# STM32F303CCT6.net
KiCad netlist of a schematic drawn in Altium Designer
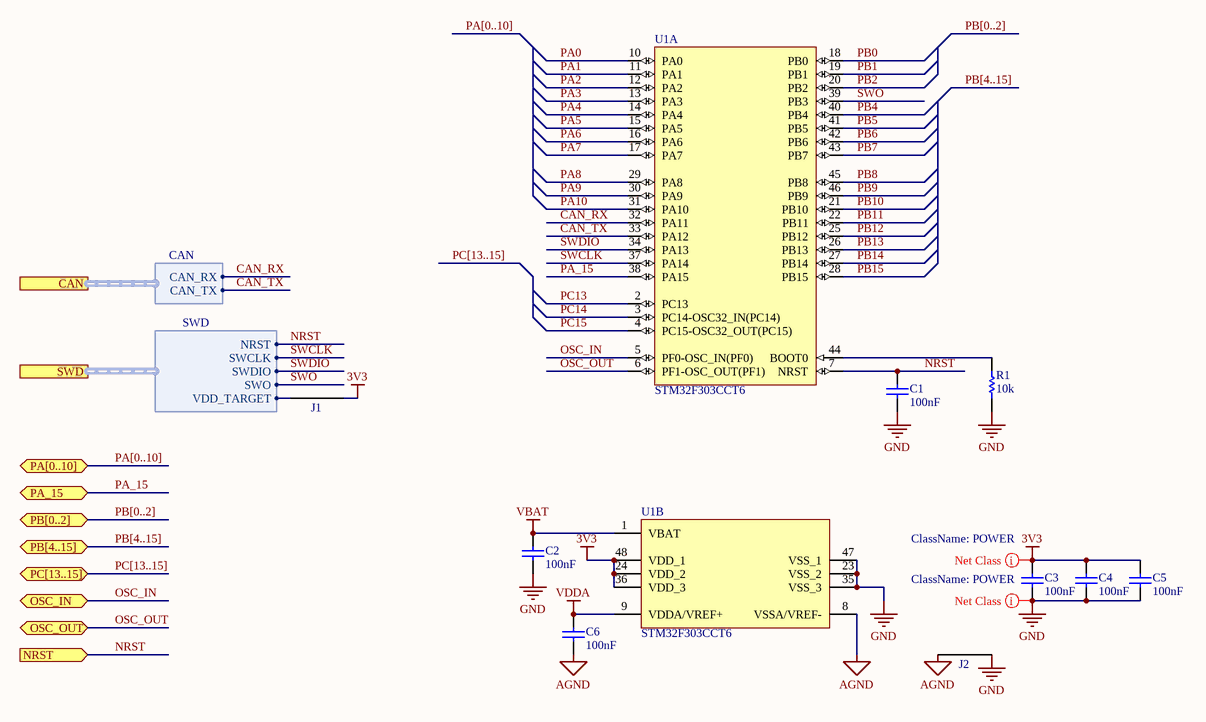
[diagram p0: STM32F303CCT6.SchDoc]

(export (version "E")
  (design (tool "Eeschema 10.0.6"))
  (components
    (comp (ref "C1")
      (value "100nF")
      (footprint "agh_racing_2018:CAP_0603_IPC_MD")
      (description "Capacitor")
      (fields (field (name "Comment") "Cap"))
      (libsource (lib "agh_racing_2018") (part "Cap"))
    )
    (comp (ref "C2")
      (value "100nF")
      (footprint "agh_racing_2018:CAP_0603_IPC_MD")
      (description "Capacitor")
      (fields (field (name "Comment") "Cap"))
      (libsource (lib "agh_racing_2018") (part "Cap"))
    )
    (comp (ref "C3")
      (value "100nF")
      (footprint "agh_racing_2018:CAP_0603_IPC_MD")
      (description "Capacitor")
      (fields (field (name "Comment") "Cap"))
      (libsource (lib "agh_racing_2018") (part "Cap"))
    )
    (comp (ref "C4")
      (value "100nF")
      (footprint "agh_racing_2018:CAP_0603_IPC_MD")
      (description "Capacitor")
      (fields (field (name "Comment") "Cap"))
      (libsource (lib "agh_racing_2018") (part "Cap"))
    )
    (comp (ref "C5")
      (value "100nF")
      (footprint "agh_racing_2018:CAP_0603_IPC_MD")
      (description "Capacitor")
      (fields (field (name "Comment") "Cap"))
      (libsource (lib "agh_racing_2018") (part "Cap"))
    )
    (comp (ref "C6")
      (value "100nF")
      (footprint "agh_racing_2018:CAP_0603_IPC_MD")
      (description "Capacitor")
      (fields (field (name "Comment") "Cap"))
      (libsource (lib "agh_racing_2018") (part "Cap"))
    )
    (comp (ref "J1")
      (value "NetTie")
      (footprint "NETTIE")
      (libsource (lib "Schematic Library") (part "NetTie"))
    )
    (comp (ref "J2")
      (value "NetTie")
      (footprint "agh_racing_2018:NETTIE")
      (libsource (lib "agh_racing_2018") (part "NetTie"))
    )
    (comp (ref "R1")
      (value "10k")
      (footprint "agh_racing_2018:RES_0603_IPC_HD")
      (description "Resistor")
      (fields (field (name "Comment") "Res"))
      (libsource (lib "agh_racing_2018") (part "Res"))
    )
    (comp (ref "U1")
      (value "STM32F303CCT6")
      (footprint "agh_racing_2018:LQFP48_IPC_LD")
      (libsource (lib "agh_racing_2018") (part "STM32F303CCT6"))
    )
  )
  (nets
    (net (code "3") (name "/CAN_RX") (class "Default")
      (node (ref "U1") (pin "32") (pinfunction "PA11_32") (pintype "bidirectional"))
    )
    (net (code "4") (name "/CAN_TX") (class "Default")
      (node (ref "U1") (pin "33") (pinfunction "PA12_33") (pintype "bidirectional"))
    )
    (net (code "5") (name "/NRST") (class "Default")
      (node (ref "C1") (pin "2") (pinfunction "2_2") (pintype "passive"))
      (node (ref "U1") (pin "7") (pinfunction "NRST_7") (pintype "bidirectional"))
    )
    (net (code "6") (name "/OSC_IN") (class "Default")
      (node (ref "U1") (pin "5") (pinfunction "PF0-OSC_IN(PF0)_5") (pintype "bidirectional"))
    )
    (net (code "7") (name "/OSC_OUT") (class "Default")
      (node (ref "U1") (pin "6") (pinfunction "PF1-OSC_OUT(PF1)_6") (pintype "bidirectional"))
    )
    (net (code "8") (name "/PA0") (class "Default")
      (node (ref "U1") (pin "10") (pinfunction "PA0_10") (pintype "bidirectional"))
    )
    (net (code "9") (name "/PA1") (class "Default")
      (node (ref "U1") (pin "11") (pinfunction "PA1_11") (pintype "bidirectional"))
    )
    (net (code "10") (name "/PA2") (class "Default")
      (node (ref "U1") (pin "12") (pinfunction "PA2_12") (pintype "bidirectional"))
    )
    (net (code "11") (name "/PA3") (class "Default")
      (node (ref "U1") (pin "13") (pinfunction "PA3_13") (pintype "bidirectional"))
    )
    (net (code "12") (name "/PA4") (class "Default")
      (node (ref "U1") (pin "14") (pinfunction "PA4_14") (pintype "bidirectional"))
    )
    (net (code "13") (name "/PA5") (class "Default")
      (node (ref "U1") (pin "15") (pinfunction "PA5_15") (pintype "bidirectional"))
    )
    (net (code "14") (name "/PA6") (class "Default")
      (node (ref "U1") (pin "16") (pinfunction "PA6_16") (pintype "bidirectional"))
    )
    (net (code "15") (name "/PA7") (class "Default")
      (node (ref "U1") (pin "17") (pinfunction "PA7_17") (pintype "bidirectional"))
    )
    (net (code "16") (name "/PA8") (class "Default")
      (node (ref "U1") (pin "29") (pinfunction "PA8_29") (pintype "bidirectional"))
    )
    (net (code "17") (name "/PA9") (class "Default")
      (node (ref "U1") (pin "30") (pinfunction "PA9_30") (pintype "bidirectional"))
    )
    (net (code "18") (name "/PA10") (class "Default")
      (node (ref "U1") (pin "31") (pinfunction "PA10_31") (pintype "bidirectional"))
    )
    (net (code "20") (name "/PA_15") (class "Default")
      (node (ref "U1") (pin "38") (pinfunction "PA15_38") (pintype "bidirectional"))
    )
    (net (code "21") (name "/PB0") (class "Default")
      (node (ref "U1") (pin "18") (pinfunction "PB0_18") (pintype "bidirectional"))
    )
    (net (code "22") (name "/PB1") (class "Default")
      (node (ref "U1") (pin "19") (pinfunction "PB1_19") (pintype "bidirectional"))
    )
    (net (code "23") (name "/PB2") (class "Default")
      (node (ref "U1") (pin "20") (pinfunction "PB2_20") (pintype "bidirectional"))
    )
    (net (code "24") (name "/PB4") (class "Default")
      (node (ref "U1") (pin "40") (pinfunction "PB4_40") (pintype "bidirectional"))
    )
    (net (code "25") (name "/PB5") (class "Default")
      (node (ref "U1") (pin "41") (pinfunction "PB5_41") (pintype "bidirectional"))
    )
    (net (code "26") (name "/PB6") (class "Default")
      (node (ref "U1") (pin "42") (pinfunction "PB6_42") (pintype "bidirectional"))
    )
    (net (code "27") (name "/PB7") (class "Default")
      (node (ref "U1") (pin "43") (pinfunction "PB7_43") (pintype "bidirectional"))
    )
    (net (code "28") (name "/PB8") (class "Default")
      (node (ref "U1") (pin "45") (pinfunction "PB8_45") (pintype "bidirectional"))
    )
    (net (code "29") (name "/PB9") (class "Default")
      (node (ref "U1") (pin "46") (pinfunction "PB9_46") (pintype "bidirectional"))
    )
    (net (code "30") (name "/PB10") (class "Default")
      (node (ref "U1") (pin "21") (pinfunction "PB10_21") (pintype "bidirectional"))
    )
    (net (code "31") (name "/PB11") (class "Default")
      (node (ref "U1") (pin "22") (pinfunction "PB11_22") (pintype "bidirectional"))
    )
    (net (code "32") (name "/PB12") (class "Default")
      (node (ref "U1") (pin "25") (pinfunction "PB12_25") (pintype "bidirectional"))
    )
    (net (code "33") (name "/PB13") (class "Default")
      (node (ref "U1") (pin "26") (pinfunction "PB13_26") (pintype "bidirectional"))
    )
    (net (code "34") (name "/PB14") (class "Default")
      (node (ref "U1") (pin "27") (pinfunction "PB14_27") (pintype "bidirectional"))
    )
    (net (code "35") (name "/PB15") (class "Default")
      (node (ref "U1") (pin "28") (pinfunction "PB15_28") (pintype "bidirectional"))
    )
    (net (code "38") (name "/PC13") (class "Default")
      (node (ref "U1") (pin "2") (pinfunction "PC13_2") (pintype "bidirectional"))
    )
    (net (code "39") (name "/PC14") (class "Default")
      (node (ref "U1") (pin "3") (pinfunction "PC14-OSC32_IN(PC14)_3") (pintype "bidirectional"))
    )
    (net (code "40") (name "/PC15") (class "Default")
      (node (ref "U1") (pin "4") (pinfunction "PC15-OSC32_OUT(PC15)_4") (pintype "bidirectional"))
    )
    (net (code "42") (name "/SWCLK") (class "Default")
      (node (ref "U1") (pin "37") (pinfunction "PA14_37") (pintype "bidirectional"))
    )
    (net (code "43") (name "/SWDIO") (class "Default")
      (node (ref "U1") (pin "34") (pinfunction "PA13_34") (pintype "bidirectional"))
    )
    (net (code "44") (name "/SWO") (class "Default")
      (node (ref "U1") (pin "39") (pinfunction "PB3_39") (pintype "bidirectional"))
    )
    (net (code "45") (name "/VDD_TARGET") (class "Default")
      (node (ref "J1") (pin "2") (pinfunction "2_2") (pintype "passive"))
    )
    (net (code "48") (name "3V3") (class "Default")
      (node (ref "C3") (pin "2") (pinfunction "2_2") (pintype "passive"))
      (node (ref "C4") (pin "2") (pinfunction "2_2") (pintype "passive"))
      (node (ref "C5") (pin "2") (pinfunction "2_2") (pintype "passive"))
      (node (ref "J1") (pin "1") (pinfunction "1_1") (pintype "passive"))
      (node (ref "U1") (pin "24") (pinfunction "VDD_2_24") (pintype "power_in"))
      (node (ref "U1") (pin "36") (pinfunction "VDD_3_36") (pintype "power_in"))
      (node (ref "U1") (pin "48") (pinfunction "VDD_1_48") (pintype "power_in"))
    )
    (net (code "49") (name "AGND") (class "Default")
      (node (ref "C6") (pin "1") (pinfunction "1_1") (pintype "passive"))
      (node (ref "J2") (pin "1") (pinfunction "1_1") (pintype "passive"))
      (node (ref "U1") (pin "8") (pinfunction "VSSA/VREF-_8") (pintype "power_in"))
    )
    (net (code "50") (name "GND") (class "Default")
      (node (ref "C1") (pin "1") (pinfunction "1_1") (pintype "passive"))
      (node (ref "C2") (pin "1") (pinfunction "1_1") (pintype "passive"))
      (node (ref "C3") (pin "1") (pinfunction "1_1") (pintype "passive"))
      (node (ref "C4") (pin "1") (pinfunction "1_1") (pintype "passive"))
      (node (ref "C5") (pin "1") (pinfunction "1_1") (pintype "passive"))
      (node (ref "J2") (pin "2") (pinfunction "2_2") (pintype "passive"))
      (node (ref "R1") (pin "1") (pinfunction "1_1") (pintype "passive"))
      (node (ref "U1") (pin "23") (pinfunction "VSS_2_23") (pintype "power_in"))
      (node (ref "U1") (pin "35") (pinfunction "VSS_3_35") (pintype "power_in"))
      (node (ref "U1") (pin "47") (pinfunction "VSS_1_47") (pintype "power_in"))
    )
    (net (code "51") (name "Net-(U1A-BOOT0)") (class "Default")
      (node (ref "R1") (pin "2") (pinfunction "2_2") (pintype "passive"))
      (node (ref "U1") (pin "44") (pinfunction "BOOT0_44") (pintype "input"))
    )
    (net (code "52") (name "VBAT") (class "Default")
      (node (ref "C2") (pin "2") (pinfunction "2_2") (pintype "passive"))
      (node (ref "U1") (pin "1") (pinfunction "VBAT_1") (pintype "power_in"))
    )
    (net (code "53") (name "VDDA") (class "Default")
      (node (ref "C6") (pin "2") (pinfunction "2_2") (pintype "passive"))
      (node (ref "U1") (pin "9") (pinfunction "VDDA/VREF+_9") (pintype "power_in"))
    )
  )
)
